# LEDARRAY.net
KiCad netlist of a schematic drawn in EAGLE
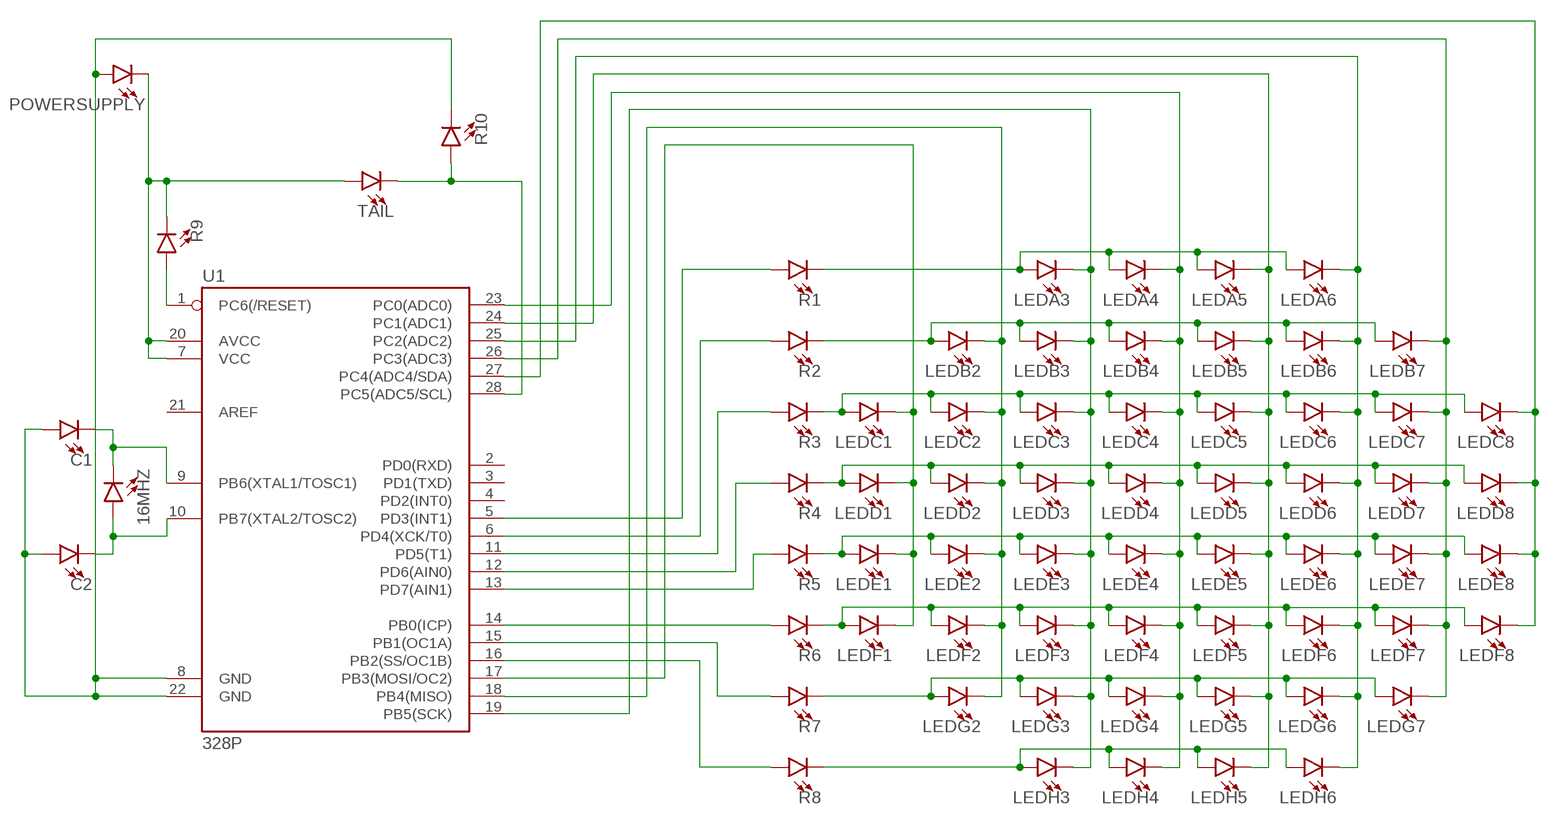
[diagram p0: schematic, sheet 1]

(export (version "E")
  (design (tool "Eeschema 10.0.6"))
  (components
    (comp (ref "16MHZ")
      (value "LED3MM")
      (footprint "eagle-import:LED_3MM")
      (libsource (lib "eagle-import") (part "LED3MM"))
    )
    (comp (ref "C1")
      (value "LED3MM")
      (footprint "eagle-import:LED_3MM")
      (libsource (lib "eagle-import") (part "LED3MM"))
    )
    (comp (ref "C2")
      (value "LED3MM")
      (footprint "eagle-import:LED_3MM")
      (libsource (lib "eagle-import") (part "LED3MM"))
    )
    (comp (ref "LEDA3")
      (value "LED3MM")
      (footprint "eagle-import:LED_3MM")
      (libsource (lib "eagle-import") (part "LED3MM"))
    )
    (comp (ref "LEDA4")
      (value "LED3MM")
      (footprint "eagle-import:LED_3MM")
      (libsource (lib "eagle-import") (part "LED3MM"))
    )
    (comp (ref "LEDA5")
      (value "LED3MM")
      (footprint "eagle-import:LED_3MM")
      (libsource (lib "eagle-import") (part "LED3MM"))
    )
    (comp (ref "LEDA6")
      (value "LED3MM")
      (footprint "eagle-import:LED_3MM")
      (libsource (lib "eagle-import") (part "LED3MM"))
    )
    (comp (ref "LEDB2")
      (value "LED3MM")
      (footprint "eagle-import:LED_3MM")
      (libsource (lib "eagle-import") (part "LED3MM"))
    )
    (comp (ref "LEDB3")
      (value "LED3MM")
      (footprint "eagle-import:LED_3MM")
      (libsource (lib "eagle-import") (part "LED3MM"))
    )
    (comp (ref "LEDB4")
      (value "LED3MM")
      (footprint "eagle-import:LED_3MM")
      (libsource (lib "eagle-import") (part "LED3MM"))
    )
    (comp (ref "LEDB5")
      (value "LED3MM")
      (footprint "eagle-import:LED_3MM")
      (libsource (lib "eagle-import") (part "LED3MM"))
    )
    (comp (ref "LEDB6")
      (value "LED3MM")
      (footprint "eagle-import:LED_3MM")
      (libsource (lib "eagle-import") (part "LED3MM"))
    )
    (comp (ref "LEDB7")
      (value "LED3MM")
      (footprint "eagle-import:LED_3MM")
      (libsource (lib "eagle-import") (part "LED3MM"))
    )
    (comp (ref "LEDC1")
      (value "LED3MM")
      (footprint "eagle-import:LED_3MM")
      (libsource (lib "eagle-import") (part "LED3MM"))
    )
    (comp (ref "LEDC2")
      (value "LED3MM")
      (footprint "eagle-import:LED_3MM")
      (libsource (lib "eagle-import") (part "LED3MM"))
    )
    (comp (ref "LEDC3")
      (value "LED3MM")
      (footprint "eagle-import:LED_3MM")
      (libsource (lib "eagle-import") (part "LED3MM"))
    )
    (comp (ref "LEDC4")
      (value "LED3MM")
      (footprint "eagle-import:LED_3MM")
      (libsource (lib "eagle-import") (part "LED3MM"))
    )
    (comp (ref "LEDC5")
      (value "LED3MM")
      (footprint "eagle-import:LED_3MM")
      (libsource (lib "eagle-import") (part "LED3MM"))
    )
    (comp (ref "LEDC6")
      (value "LED3MM")
      (footprint "eagle-import:LED_3MM")
      (libsource (lib "eagle-import") (part "LED3MM"))
    )
    (comp (ref "LEDC7")
      (value "LED3MM")
      (footprint "eagle-import:LED_3MM")
      (libsource (lib "eagle-import") (part "LED3MM"))
    )
    (comp (ref "LEDC8")
      (value "LED3MM")
      (footprint "eagle-import:LED_3MM")
      (libsource (lib "eagle-import") (part "LED3MM"))
    )
    (comp (ref "LEDD1")
      (value "LED3MM")
      (footprint "eagle-import:LED_3MM")
      (libsource (lib "eagle-import") (part "LED3MM"))
    )
    (comp (ref "LEDD2")
      (value "LED3MM")
      (footprint "eagle-import:LED_3MM")
      (libsource (lib "eagle-import") (part "LED3MM"))
    )
    (comp (ref "LEDD3")
      (value "LED3MM")
      (footprint "eagle-import:LED_3MM")
      (libsource (lib "eagle-import") (part "LED3MM"))
    )
    (comp (ref "LEDD4")
      (value "LED3MM")
      (footprint "eagle-import:LED_3MM")
      (libsource (lib "eagle-import") (part "LED3MM"))
    )
    (comp (ref "LEDD5")
      (value "LED3MM")
      (footprint "eagle-import:LED_3MM")
      (libsource (lib "eagle-import") (part "LED3MM"))
    )
    (comp (ref "LEDD6")
      (value "LED3MM")
      (footprint "eagle-import:LED_3MM")
      (libsource (lib "eagle-import") (part "LED3MM"))
    )
    (comp (ref "LEDD7")
      (value "LED3MM")
      (footprint "eagle-import:LED_3MM")
      (libsource (lib "eagle-import") (part "LED3MM"))
    )
    (comp (ref "LEDD8")
      (value "LED3MM")
      (footprint "eagle-import:LED_3MM")
      (libsource (lib "eagle-import") (part "LED3MM"))
    )
    (comp (ref "LEDE1")
      (value "LED3MM")
      (footprint "eagle-import:LED_3MM")
      (libsource (lib "eagle-import") (part "LED3MM"))
    )
    (comp (ref "LEDE2")
      (value "LED3MM")
      (footprint "eagle-import:LED_3MM")
      (libsource (lib "eagle-import") (part "LED3MM"))
    )
    (comp (ref "LEDE3")
      (value "LED3MM")
      (footprint "eagle-import:LED_3MM")
      (libsource (lib "eagle-import") (part "LED3MM"))
    )
    (comp (ref "LEDE4")
      (value "LED3MM")
      (footprint "eagle-import:LED_3MM")
      (libsource (lib "eagle-import") (part "LED3MM"))
    )
    (comp (ref "LEDE5")
      (value "LED3MM")
      (footprint "eagle-import:LED_3MM")
      (libsource (lib "eagle-import") (part "LED3MM"))
    )
    (comp (ref "LEDE6")
      (value "LED3MM")
      (footprint "eagle-import:LED_3MM")
      (libsource (lib "eagle-import") (part "LED3MM"))
    )
    (comp (ref "LEDE7")
      (value "LED3MM")
      (footprint "eagle-import:LED_3MM")
      (libsource (lib "eagle-import") (part "LED3MM"))
    )
    (comp (ref "LEDE8")
      (value "LED3MM")
      (footprint "eagle-import:LED_3MM")
      (libsource (lib "eagle-import") (part "LED3MM"))
    )
    (comp (ref "LEDF1")
      (value "LED3MM")
      (footprint "eagle-import:LED_3MM")
      (libsource (lib "eagle-import") (part "LED3MM"))
    )
    (comp (ref "LEDF2")
      (value "LED3MM")
      (footprint "eagle-import:LED_3MM")
      (libsource (lib "eagle-import") (part "LED3MM"))
    )
    (comp (ref "LEDF3")
      (value "LED3MM")
      (footprint "eagle-import:LED_3MM")
      (libsource (lib "eagle-import") (part "LED3MM"))
    )
    (comp (ref "LEDF4")
      (value "LED3MM")
      (footprint "eagle-import:LED_3MM")
      (libsource (lib "eagle-import") (part "LED3MM"))
    )
    (comp (ref "LEDF5")
      (value "LED3MM")
      (footprint "eagle-import:LED_3MM")
      (libsource (lib "eagle-import") (part "LED3MM"))
    )
    (comp (ref "LEDF6")
      (value "LED3MM")
      (footprint "eagle-import:LED_3MM")
      (libsource (lib "eagle-import") (part "LED3MM"))
    )
    (comp (ref "LEDF7")
      (value "LED3MM")
      (footprint "eagle-import:LED_3MM")
      (libsource (lib "eagle-import") (part "LED3MM"))
    )
    (comp (ref "LEDF8")
      (value "LED3MM")
      (footprint "eagle-import:LED_3MM")
      (libsource (lib "eagle-import") (part "LED3MM"))
    )
    (comp (ref "LEDG2")
      (value "LED3MM")
      (footprint "eagle-import:LED_3MM")
      (libsource (lib "eagle-import") (part "LED3MM"))
    )
    (comp (ref "LEDG3")
      (value "LED3MM")
      (footprint "eagle-import:LED_3MM")
      (libsource (lib "eagle-import") (part "LED3MM"))
    )
    (comp (ref "LEDG4")
      (value "LED3MM")
      (footprint "eagle-import:LED_3MM")
      (libsource (lib "eagle-import") (part "LED3MM"))
    )
    (comp (ref "LEDG5")
      (value "LED3MM")
      (footprint "eagle-import:LED_3MM")
      (libsource (lib "eagle-import") (part "LED3MM"))
    )
    (comp (ref "LEDG6")
      (value "LED3MM")
      (footprint "eagle-import:LED_3MM")
      (libsource (lib "eagle-import") (part "LED3MM"))
    )
    (comp (ref "LEDG7")
      (value "LED3MM")
      (footprint "eagle-import:LED_3MM")
      (libsource (lib "eagle-import") (part "LED3MM"))
    )
    (comp (ref "LEDH3")
      (value "LED3MM")
      (footprint "eagle-import:LED_3MM")
      (libsource (lib "eagle-import") (part "LED3MM"))
    )
    (comp (ref "LEDH4")
      (value "LED3MM")
      (footprint "eagle-import:LED_3MM")
      (libsource (lib "eagle-import") (part "LED3MM"))
    )
    (comp (ref "LEDH5")
      (value "LED3MM")
      (footprint "eagle-import:LED_3MM")
      (libsource (lib "eagle-import") (part "LED3MM"))
    )
    (comp (ref "LEDH6")
      (value "LED3MM")
      (footprint "eagle-import:LED_3MM")
      (libsource (lib "eagle-import") (part "LED3MM"))
    )
    (comp (ref "POWERSUPPLY")
      (value "LED3MM")
      (footprint "eagle-import:LED_3MM")
      (libsource (lib "eagle-import") (part "LED3MM"))
    )
    (comp (ref "R1")
      (value "LED3MM")
      (footprint "eagle-import:LED_3MM")
      (libsource (lib "eagle-import") (part "LED3MM"))
    )
    (comp (ref "R2")
      (value "LED3MM")
      (footprint "eagle-import:LED_3MM")
      (libsource (lib "eagle-import") (part "LED3MM"))
    )
    (comp (ref "R3")
      (value "LED3MM")
      (footprint "eagle-import:LED_3MM")
      (libsource (lib "eagle-import") (part "LED3MM"))
    )
    (comp (ref "R4")
      (value "LED3MM")
      (footprint "eagle-import:LED_3MM")
      (libsource (lib "eagle-import") (part "LED3MM"))
    )
    (comp (ref "R5")
      (value "LED3MM")
      (footprint "eagle-import:LED_3MM")
      (libsource (lib "eagle-import") (part "LED3MM"))
    )
    (comp (ref "R6")
      (value "LED3MM")
      (footprint "eagle-import:LED_3MM")
      (libsource (lib "eagle-import") (part "LED3MM"))
    )
    (comp (ref "R7")
      (value "LED3MM")
      (footprint "eagle-import:LED_3MM")
      (libsource (lib "eagle-import") (part "LED3MM"))
    )
    (comp (ref "R8")
      (value "LED3MM")
      (footprint "eagle-import:LED_3MM")
      (libsource (lib "eagle-import") (part "LED3MM"))
    )
    (comp (ref "R9")
      (value "LED3MM")
      (footprint "eagle-import:LED_3MM")
      (libsource (lib "eagle-import") (part "LED3MM"))
    )
    (comp (ref "R10")
      (value "LED3MM")
      (footprint "eagle-import:LED_3MM")
      (libsource (lib "eagle-import") (part "LED3MM"))
    )
    (comp (ref "TAIL")
      (value "LED3MM")
      (footprint "eagle-import:LED_3MM")
      (libsource (lib "eagle-import") (part "LED3MM"))
    )
    (comp (ref "U1")
      (value "328P")
      (footprint "eagle-import:DIP28")
      (libsource (lib "eagle-import") (part "ATMEGA328P_PDIP"))
    )
  )
  (nets
    (net (code "1") (name "Net-(16MHZ-C)") (class "Default")
      (node (ref "16MHZ") (pin "K") (pinfunction "C_K") (pintype "passive"))
      (node (ref "C1") (pin "K") (pinfunction "C_K") (pintype "passive"))
      (node (ref "U1") (pin "9") (pinfunction "PB6(XTAL1/TOSC1)_9") (pintype "bidirectional"))
    )
    (net (code "2") (name "Net-(C2-C)") (class "Default")
      (node (ref "16MHZ") (pin "A") (pinfunction "A_A") (pintype "passive"))
      (node (ref "C2") (pin "K") (pinfunction "C_K") (pintype "passive"))
      (node (ref "U1") (pin "10") (pinfunction "PB7(XTAL2/TOSC2)_10") (pintype "bidirectional"))
    )
    (net (code "3") (name "Net-(LEDA3-C)") (class "Default")
      (node (ref "LEDA3") (pin "K") (pinfunction "C_K") (pintype "passive"))
      (node (ref "LEDB3") (pin "K") (pinfunction "C_K") (pintype "passive"))
      (node (ref "LEDC3") (pin "K") (pinfunction "C_K") (pintype "passive"))
      (node (ref "LEDD3") (pin "K") (pinfunction "C_K") (pintype "passive"))
      (node (ref "LEDE3") (pin "K") (pinfunction "C_K") (pintype "passive"))
      (node (ref "LEDF3") (pin "K") (pinfunction "C_K") (pintype "passive"))
      (node (ref "LEDG3") (pin "K") (pinfunction "C_K") (pintype "passive"))
      (node (ref "LEDH3") (pin "K") (pinfunction "C_K") (pintype "passive"))
      (node (ref "U1") (pin "19") (pinfunction "PB5(SCK)_19") (pintype "bidirectional"))
    )
    (net (code "4") (name "Net-(LEDA4-C)") (class "Default")
      (node (ref "LEDA4") (pin "K") (pinfunction "C_K") (pintype "passive"))
      (node (ref "LEDB4") (pin "K") (pinfunction "C_K") (pintype "passive"))
      (node (ref "LEDC4") (pin "K") (pinfunction "C_K") (pintype "passive"))
      (node (ref "LEDD4") (pin "K") (pinfunction "C_K") (pintype "passive"))
      (node (ref "LEDE4") (pin "K") (pinfunction "C_K") (pintype "passive"))
      (node (ref "LEDF4") (pin "K") (pinfunction "C_K") (pintype "passive"))
      (node (ref "LEDG4") (pin "K") (pinfunction "C_K") (pintype "passive"))
      (node (ref "LEDH4") (pin "K") (pinfunction "C_K") (pintype "passive"))
      (node (ref "U1") (pin "23") (pinfunction "PC0(ADC0)_23") (pintype "bidirectional"))
    )
    (net (code "5") (name "Net-(LEDA5-C)") (class "Default")
      (node (ref "LEDA5") (pin "K") (pinfunction "C_K") (pintype "passive"))
      (node (ref "LEDB5") (pin "K") (pinfunction "C_K") (pintype "passive"))
      (node (ref "LEDC5") (pin "K") (pinfunction "C_K") (pintype "passive"))
      (node (ref "LEDD5") (pin "K") (pinfunction "C_K") (pintype "passive"))
      (node (ref "LEDE5") (pin "K") (pinfunction "C_K") (pintype "passive"))
      (node (ref "LEDF5") (pin "K") (pinfunction "C_K") (pintype "passive"))
      (node (ref "LEDG5") (pin "K") (pinfunction "C_K") (pintype "passive"))
      (node (ref "LEDH5") (pin "K") (pinfunction "C_K") (pintype "passive"))
      (node (ref "U1") (pin "24") (pinfunction "PC1(ADC1)_24") (pintype "bidirectional"))
    )
    (net (code "6") (name "Net-(LEDA6-C)") (class "Default")
      (node (ref "LEDA6") (pin "K") (pinfunction "C_K") (pintype "passive"))
      (node (ref "LEDB6") (pin "K") (pinfunction "C_K") (pintype "passive"))
      (node (ref "LEDC6") (pin "K") (pinfunction "C_K") (pintype "passive"))
      (node (ref "LEDD6") (pin "K") (pinfunction "C_K") (pintype "passive"))
      (node (ref "LEDE6") (pin "K") (pinfunction "C_K") (pintype "passive"))
      (node (ref "LEDF6") (pin "K") (pinfunction "C_K") (pintype "passive"))
      (node (ref "LEDG6") (pin "K") (pinfunction "C_K") (pintype "passive"))
      (node (ref "LEDH6") (pin "K") (pinfunction "C_K") (pintype "passive"))
      (node (ref "U1") (pin "25") (pinfunction "PC2(ADC2)_25") (pintype "bidirectional"))
    )
    (net (code "7") (name "Net-(LEDB2-C)") (class "Default")
      (node (ref "LEDB2") (pin "K") (pinfunction "C_K") (pintype "passive"))
      (node (ref "LEDC2") (pin "K") (pinfunction "C_K") (pintype "passive"))
      (node (ref "LEDD2") (pin "K") (pinfunction "C_K") (pintype "passive"))
      (node (ref "LEDE2") (pin "K") (pinfunction "C_K") (pintype "passive"))
      (node (ref "LEDF2") (pin "K") (pinfunction "C_K") (pintype "passive"))
      (node (ref "LEDG2") (pin "K") (pinfunction "C_K") (pintype "passive"))
      (node (ref "U1") (pin "18") (pinfunction "PB4(MISO)_18") (pintype "bidirectional"))
    )
    (net (code "8") (name "Net-(LEDB7-C)") (class "Default")
      (node (ref "LEDB7") (pin "K") (pinfunction "C_K") (pintype "passive"))
      (node (ref "LEDC7") (pin "K") (pinfunction "C_K") (pintype "passive"))
      (node (ref "LEDD7") (pin "K") (pinfunction "C_K") (pintype "passive"))
      (node (ref "LEDE7") (pin "K") (pinfunction "C_K") (pintype "passive"))
      (node (ref "LEDF7") (pin "K") (pinfunction "C_K") (pintype "passive"))
      (node (ref "LEDG7") (pin "K") (pinfunction "C_K") (pintype "passive"))
      (node (ref "U1") (pin "26") (pinfunction "PC3(ADC3)_26") (pintype "bidirectional"))
    )
    (net (code "9") (name "Net-(LEDC1-C)") (class "Default")
      (node (ref "LEDC1") (pin "K") (pinfunction "C_K") (pintype "passive"))
      (node (ref "LEDD1") (pin "K") (pinfunction "C_K") (pintype "passive"))
      (node (ref "LEDE1") (pin "K") (pinfunction "C_K") (pintype "passive"))
      (node (ref "LEDF1") (pin "K") (pinfunction "C_K") (pintype "passive"))
      (node (ref "U1") (pin "17") (pinfunction "PB3(MOSI/OC2)_17") (pintype "bidirectional"))
    )
    (net (code "10") (name "Net-(LEDC8-C)") (class "Default")
      (node (ref "LEDC8") (pin "K") (pinfunction "C_K") (pintype "passive"))
      (node (ref "LEDD8") (pin "K") (pinfunction "C_K") (pintype "passive"))
      (node (ref "LEDE8") (pin "K") (pinfunction "C_K") (pintype "passive"))
      (node (ref "LEDF8") (pin "K") (pinfunction "C_K") (pintype "passive"))
      (node (ref "U1") (pin "27") (pinfunction "PC4(ADC4/SDA)_27") (pintype "bidirectional"))
    )
    (net (code "11") (name "Net-(POWERSUPPLY-C)") (class "Default")
      (node (ref "POWERSUPPLY") (pin "K") (pinfunction "C_K") (pintype "passive"))
      (node (ref "R9") (pin "K") (pinfunction "C_K") (pintype "passive"))
      (node (ref "TAIL") (pin "A") (pinfunction "A_A") (pintype "passive"))
      (node (ref "U1") (pin "20") (pinfunction "AVCC_20") (pintype "bidirectional"))
      (node (ref "U1") (pin "7") (pinfunction "VCC_7") (pintype "bidirectional"))
    )
    (net (code "12") (name "Net-(R1-C)") (class "Default")
      (node (ref "LEDA3") (pin "A") (pinfunction "A_A") (pintype "passive"))
      (node (ref "LEDA4") (pin "A") (pinfunction "A_A") (pintype "passive"))
      (node (ref "LEDA5") (pin "A") (pinfunction "A_A") (pintype "passive"))
      (node (ref "LEDA6") (pin "A") (pinfunction "A_A") (pintype "passive"))
      (node (ref "R1") (pin "K") (pinfunction "C_K") (pintype "passive"))
    )
    (net (code "13") (name "Net-(R2-C)") (class "Default")
      (node (ref "LEDB2") (pin "A") (pinfunction "A_A") (pintype "passive"))
      (node (ref "LEDB3") (pin "A") (pinfunction "A_A") (pintype "passive"))
      (node (ref "LEDB4") (pin "A") (pinfunction "A_A") (pintype "passive"))
      (node (ref "LEDB5") (pin "A") (pinfunction "A_A") (pintype "passive"))
      (node (ref "LEDB6") (pin "A") (pinfunction "A_A") (pintype "passive"))
      (node (ref "LEDB7") (pin "A") (pinfunction "A_A") (pintype "passive"))
      (node (ref "R2") (pin "K") (pinfunction "C_K") (pintype "passive"))
    )
    (net (code "14") (name "Net-(R3-C)") (class "Default")
      (node (ref "LEDC1") (pin "A") (pinfunction "A_A") (pintype "passive"))
      (node (ref "LEDC2") (pin "A") (pinfunction "A_A") (pintype "passive"))
      (node (ref "LEDC3") (pin "A") (pinfunction "A_A") (pintype "passive"))
      (node (ref "LEDC4") (pin "A") (pinfunction "A_A") (pintype "passive"))
      (node (ref "LEDC5") (pin "A") (pinfunction "A_A") (pintype "passive"))
      (node (ref "LEDC6") (pin "A") (pinfunction "A_A") (pintype "passive"))
      (node (ref "LEDC7") (pin "A") (pinfunction "A_A") (pintype "passive"))
      (node (ref "LEDC8") (pin "A") (pinfunction "A_A") (pintype "passive"))
      (node (ref "R3") (pin "K") (pinfunction "C_K") (pintype "passive"))
    )
    (net (code "15") (name "Net-(R4-C)") (class "Default")
      (node (ref "LEDD1") (pin "A") (pinfunction "A_A") (pintype "passive"))
      (node (ref "LEDD2") (pin "A") (pinfunction "A_A") (pintype "passive"))
      (node (ref "LEDD3") (pin "A") (pinfunction "A_A") (pintype "passive"))
      (node (ref "LEDD4") (pin "A") (pinfunction "A_A") (pintype "passive"))
      (node (ref "LEDD5") (pin "A") (pinfunction "A_A") (pintype "passive"))
      (node (ref "LEDD6") (pin "A") (pinfunction "A_A") (pintype "passive"))
      (node (ref "LEDD7") (pin "A") (pinfunction "A_A") (pintype "passive"))
      (node (ref "LEDD8") (pin "A") (pinfunction "A_A") (pintype "passive"))
      (node (ref "R4") (pin "K") (pinfunction "C_K") (pintype "passive"))
    )
    (net (code "16") (name "Net-(R5-C)") (class "Default")
      (node (ref "LEDE1") (pin "A") (pinfunction "A_A") (pintype "passive"))
      (node (ref "LEDE2") (pin "A") (pinfunction "A_A") (pintype "passive"))
      (node (ref "LEDE3") (pin "A") (pinfunction "A_A") (pintype "passive"))
      (node (ref "LEDE4") (pin "A") (pinfunction "A_A") (pintype "passive"))
      (node (ref "LEDE5") (pin "A") (pinfunction "A_A") (pintype "passive"))
      (node (ref "LEDE6") (pin "A") (pinfunction "A_A") (pintype "passive"))
      (node (ref "LEDE7") (pin "A") (pinfunction "A_A") (pintype "passive"))
      (node (ref "LEDE8") (pin "A") (pinfunction "A_A") (pintype "passive"))
      (node (ref "R5") (pin "K") (pinfunction "C_K") (pintype "passive"))
    )
    (net (code "17") (name "Net-(R6-C)") (class "Default")
      (node (ref "LEDF1") (pin "A") (pinfunction "A_A") (pintype "passive"))
      (node (ref "LEDF2") (pin "A") (pinfunction "A_A") (pintype "passive"))
      (node (ref "LEDF3") (pin "A") (pinfunction "A_A") (pintype "passive"))
      (node (ref "LEDF4") (pin "A") (pinfunction "A_A") (pintype "passive"))
      (node (ref "LEDF5") (pin "A") (pinfunction "A_A") (pintype "passive"))
      (node (ref "LEDF6") (pin "A") (pinfunction "A_A") (pintype "passive"))
      (node (ref "LEDF7") (pin "A") (pinfunction "A_A") (pintype "passive"))
      (node (ref "LEDF8") (pin "A") (pinfunction "A_A") (pintype "passive"))
      (node (ref "R6") (pin "K") (pinfunction "C_K") (pintype "passive"))
    )
    (net (code "18") (name "Net-(R7-C)") (class "Default")
      (node (ref "LEDG2") (pin "A") (pinfunction "A_A") (pintype "passive"))
      (node (ref "LEDG3") (pin "A") (pinfunction "A_A") (pintype "passive"))
      (node (ref "LEDG4") (pin "A") (pinfunction "A_A") (pintype "passive"))
      (node (ref "LEDG5") (pin "A") (pinfunction "A_A") (pintype "passive"))
      (node (ref "LEDG6") (pin "A") (pinfunction "A_A") (pintype "passive"))
      (node (ref "LEDG7") (pin "A") (pinfunction "A_A") (pintype "passive"))
      (node (ref "R7") (pin "K") (pinfunction "C_K") (pintype "passive"))
    )
    (net (code "19") (name "Net-(R8-C)") (class "Default")
      (node (ref "LEDH3") (pin "A") (pinfunction "A_A") (pintype "passive"))
      (node (ref "LEDH4") (pin "A") (pinfunction "A_A") (pintype "passive"))
      (node (ref "LEDH5") (pin "A") (pinfunction "A_A") (pintype "passive"))
      (node (ref "LEDH6") (pin "A") (pinfunction "A_A") (pintype "passive"))
      (node (ref "R8") (pin "K") (pinfunction "C_K") (pintype "passive"))
    )
    (net (code "20") (name "Net-(R10-C)") (class "Default")
      (node (ref "C1") (pin "A") (pinfunction "A_A") (pintype "passive"))
      (node (ref "C2") (pin "A") (pinfunction "A_A") (pintype "passive"))
      (node (ref "POWERSUPPLY") (pin "A") (pinfunction "A_A") (pintype "passive"))
      (node (ref "R10") (pin "K") (pinfunction "C_K") (pintype "passive"))
      (node (ref "U1") (pin "22") (pinfunction "GND_22") (pintype "bidirectional"))
      (node (ref "U1") (pin "8") (pinfunction "GND_8") (pintype "bidirectional"))
    )
    (net (code "21") (name "Net-(TAIL-C)") (class "Default")
      (node (ref "R10") (pin "A") (pinfunction "A_A") (pintype "passive"))
      (node (ref "TAIL") (pin "K") (pinfunction "C_K") (pintype "passive"))
      (node (ref "U1") (pin "28") (pinfunction "PC5(ADC5/SCL)_28") (pintype "bidirectional"))
    )
    (net (code "22") (name "Net-(U1-PB0(ICP))") (class "Default")
      (node (ref "R6") (pin "A") (pinfunction "A_A") (pintype "passive"))
      (node (ref "U1") (pin "14") (pinfunction "PB0(ICP)_14") (pintype "bidirectional"))
    )
    (net (code "23") (name "Net-(U1-PB1(OC1A))") (class "Default")
      (node (ref "R7") (pin "A") (pinfunction "A_A") (pintype "passive"))
      (node (ref "U1") (pin "15") (pinfunction "PB1(OC1A)_15") (pintype "bidirectional"))
    )
    (net (code "24") (name "Net-(U1-PB2(SS{slash}OC1B))") (class "Default")
      (node (ref "R8") (pin "A") (pinfunction "A_A") (pintype "passive"))
      (node (ref "U1") (pin "16") (pinfunction "PB2(SS/OC1B)_16") (pintype "bidirectional"))
    )
    (net (code "25") (name "Net-(U1-PC6({slash}RESET))") (class "Default")
      (node (ref "R9") (pin "A") (pinfunction "A_A") (pintype "passive"))
      (node (ref "U1") (pin "1") (pinfunction "PC6(/RESET)_1") (pintype "bidirectional"))
    )
    (net (code "26") (name "Net-(U1-PD3(INT1))") (class "Default")
      (node (ref "R1") (pin "A") (pinfunction "A_A") (pintype "passive"))
      (node (ref "U1") (pin "5") (pinfunction "PD3(INT1)_5") (pintype "bidirectional"))
    )
    (net (code "27") (name "Net-(U1-PD4(XCK{slash}T0))") (class "Default")
      (node (ref "R2") (pin "A") (pinfunction "A_A") (pintype "passive"))
      (node (ref "U1") (pin "6") (pinfunction "PD4(XCK/T0)_6") (pintype "bidirectional"))
    )
    (net (code "28") (name "Net-(U1-PD5(T1))") (class "Default")
      (node (ref "R3") (pin "A") (pinfunction "A_A") (pintype "passive"))
      (node (ref "U1") (pin "11") (pinfunction "PD5(T1)_11") (pintype "bidirectional"))
    )
    (net (code "29") (name "Net-(U1-PD6(AIN0))") (class "Default")
      (node (ref "R4") (pin "A") (pinfunction "A_A") (pintype "passive"))
      (node (ref "U1") (pin "12") (pinfunction "PD6(AIN0)_12") (pintype "bidirectional"))
    )
    (net (code "30") (name "Net-(U1-PD7(AIN1))") (class "Default")
      (node (ref "R5") (pin "A") (pinfunction "A_A") (pintype "passive"))
      (node (ref "U1") (pin "13") (pinfunction "PD7(AIN1)_13") (pintype "bidirectional"))
    )
    (net (code "31") (name "unconnected-(U1-AREF-Pad21)") (class "Default")
      (node (ref "U1") (pin "21") (pinfunction "AREF_21") (pintype "bidirectional"))
    )
    (net (code "32") (name "unconnected-(U1-PD0(RXD)-Pad2)") (class "Default")
      (node (ref "U1") (pin "2") (pinfunction "PD0(RXD)_2") (pintype "bidirectional"))
    )
    (net (code "33") (name "unconnected-(U1-PD1(TXD)-Pad3)") (class "Default")
      (node (ref "U1") (pin "3") (pinfunction "PD1(TXD)_3") (pintype "bidirectional"))
    )
    (net (code "34") (name "unconnected-(U1-PD2(INT0)-Pad4)") (class "Default")
      (node (ref "U1") (pin "4") (pinfunction "PD2(INT0)_4") (pintype "bidirectional"))
    )
  )
)
